# OLD-URC_ezFET_Lite.net
KiCad netlist of a schematic drawn in Altium Designer
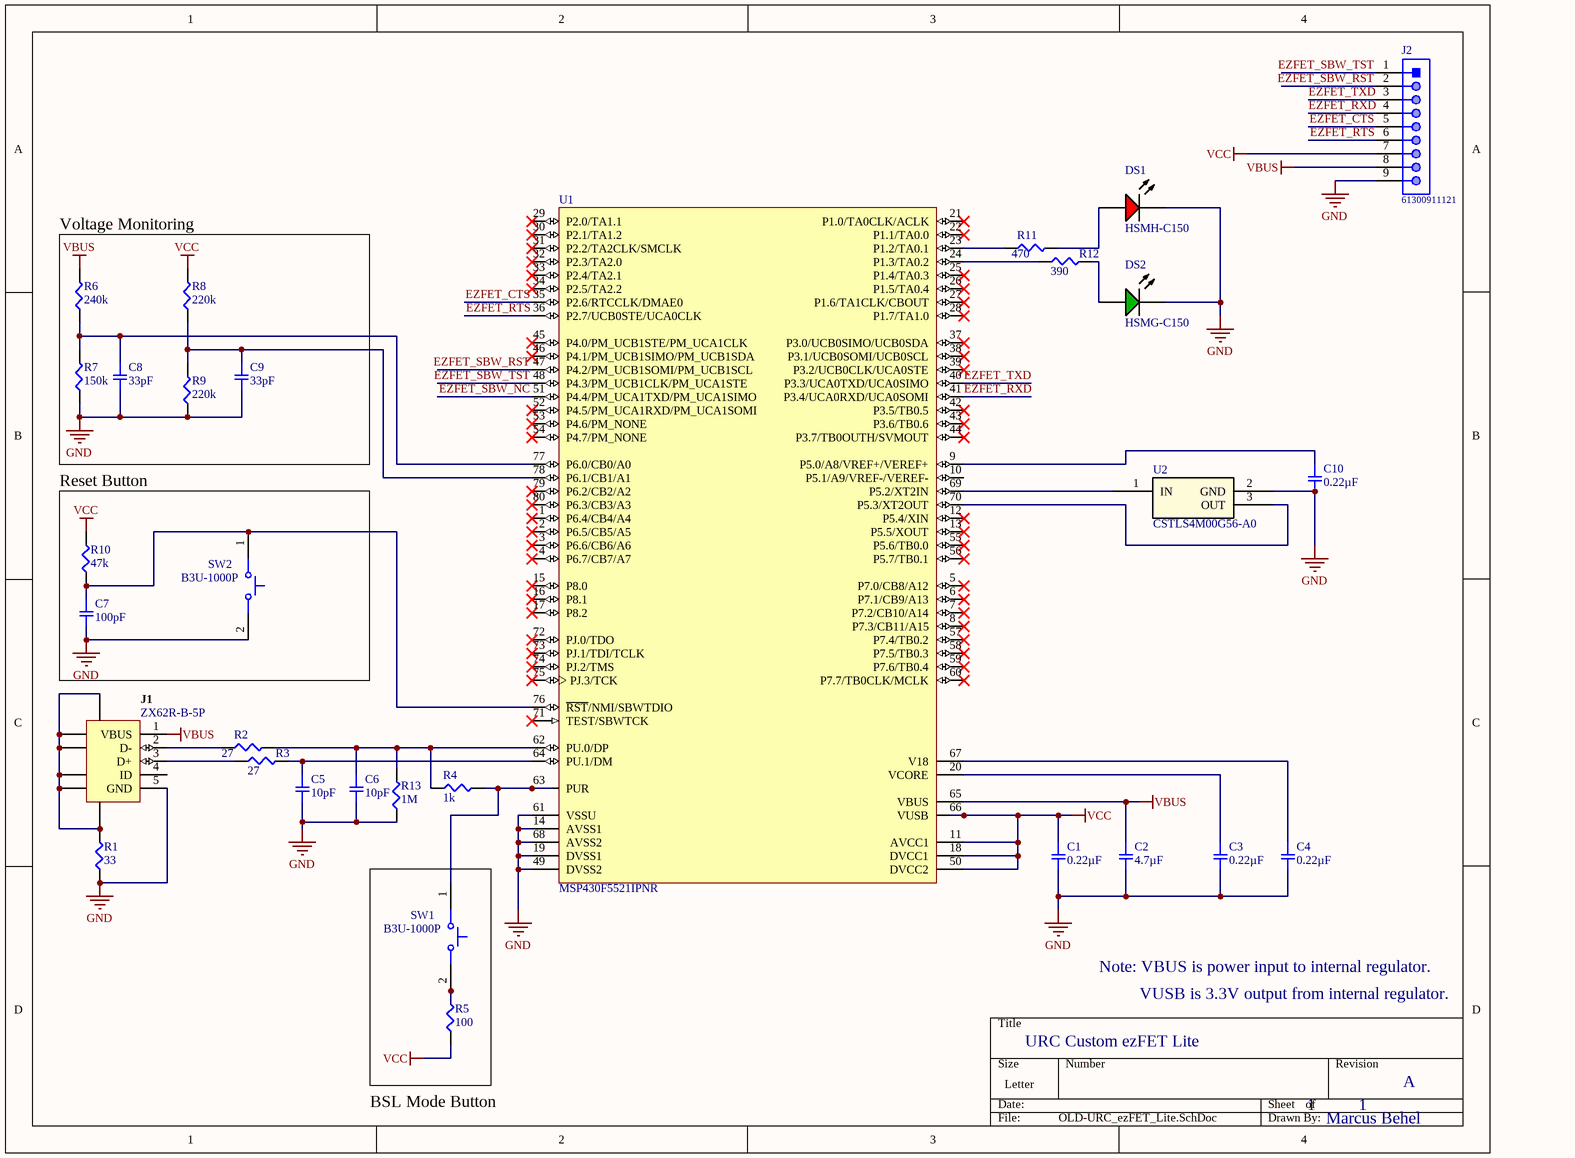
[diagram p0: OLD-URC_ezFET_Lite.SchDoc]

(export (version "E")
  (design (tool "Eeschema 10.0.6"))
  (components
    (comp (ref "C1")
      (value "0.22µF")
      (footprint "SMD-1206C")
      (description "CAP CER 0.22UF 50V X7R 1206")
      (fields
        (field (name "DIGI-KEY PART NUMBER") "490-8059-1-ND")
        (field (name "PART NUMBER") "GCM31MR71H224KA37L")
      )
      (libsource (lib "capacitor_murata_1206$") (part "GCM31MR71H224KA37L"))
    )
    (comp (ref "C2")
      (value "4.7µF")
      (footprint "SMD-1206C")
      (description "CAP CER 4.7UF 25V X7R 1206")
      (fields
        (field (name "DIGI-KEY PART NUMBER") "490-5808-1-ND")
        (field (name "PART NUMBER") "GCJ31CR71E475KA12L")
      )
      (libsource (lib "capacitor_murata_1206$") (part "GCJ31CR71E475KA12L"))
    )
    (comp (ref "C3")
      (value "0.22µF")
      (footprint "SMD-1206C")
      (description "CAP CER 0.22UF 50V X7R 1206")
      (fields
        (field (name "DIGI-KEY PART NUMBER") "490-8059-1-ND")
        (field (name "PART NUMBER") "GCM31MR71H224KA37L")
      )
      (libsource (lib "capacitor_murata_1206$") (part "GCM31MR71H224KA37L"))
    )
    (comp (ref "C4")
      (value "0.22µF")
      (footprint "SMD-1206C")
      (description "CAP CER 0.22UF 50V X7R 1206")
      (fields
        (field (name "DIGI-KEY PART NUMBER") "490-8059-1-ND")
        (field (name "PART NUMBER") "GCM31MR71H224KA37L")
      )
      (libsource (lib "capacitor_murata_1206$") (part "GCM31MR71H224KA37L"))
    )
    (comp (ref "C5")
      (value "10pF")
      (footprint "SMD-1206C")
      (description "CAP CER 10PF 630V U2J 1206")
      (fields
        (field (name "DIGI-KEY PART NUMBER") "490-5037-1-ND")
        (field (name "PART NUMBER") "GCM31A7U2J100JX01D")
      )
      (libsource (lib "capacitor_murata_1206$") (part "GCM31A7U2J100JX01D"))
    )
    (comp (ref "C6")
      (value "10pF")
      (footprint "SMD-1206C")
      (description "CAP CER 10PF 630V U2J 1206")
      (fields
        (field (name "DIGI-KEY PART NUMBER") "490-5037-1-ND")
        (field (name "PART NUMBER") "GCM31A7U2J100JX01D")
      )
      (libsource (lib "capacitor_murata_1206$") (part "GCM31A7U2J100JX01D"))
    )
    (comp (ref "C7")
      (value "100pF")
      (footprint "SMD-1206C")
      (description "CAP CER 100PF 630V U2J 1206")
      (fields
        (field (name "DIGI-KEY PART NUMBER") "490-5043-1-ND")
        (field (name "PART NUMBER") "GCM31A7U2J101JX01D")
      )
      (libsource (lib "capacitor_murata_1206$") (part "GCM31A7U2J101JX01D"))
    )
    (comp (ref "C8")
      (value "33pF")
      (footprint "SMD-1206C")
      (description "CAP CER 33PF 630V U2J 1206")
      (fields
        (field (name "DIGI-KEY PART NUMBER") "490-5040-1-ND")
        (field (name "PART NUMBER") "GCM31A7U2J330JX01D")
      )
      (libsource (lib "capacitor_murata_1206$") (part "GCM31A7U2J330JX01D"))
    )
    (comp (ref "C9")
      (value "33pF")
      (footprint "SMD-1206C")
      (description "CAP CER 33PF 630V U2J 1206")
      (fields
        (field (name "DIGI-KEY PART NUMBER") "490-5040-1-ND")
        (field (name "PART NUMBER") "GCM31A7U2J330JX01D")
      )
      (libsource (lib "capacitor_murata_1206$") (part "GCM31A7U2J330JX01D"))
    )
    (comp (ref "C10")
      (value "0.22µF")
      (footprint "SMD-1206C")
      (description "CAP CER 0.22UF 50V X7R 1206")
      (fields
        (field (name "DIGI-KEY PART NUMBER") "490-8059-1-ND")
        (field (name "PART NUMBER") "GCM31MR71H224KA37L")
      )
      (libsource (lib "capacitor_murata_1206$") (part "GCM31MR71H224KA37L"))
    )
    (comp (ref "DS1")
      (value "HSMH-C150")
      (footprint "AVAG-HSMX-C150_V")
      (description "LED Uni-Color Red, 65 mW, 25 mA, -40 to 85 degC, 2-Pin SMD, RoHS, Tape and Reel")
      (fields (field (name "MANUFACTURER") "Avago"))
      (libsource (lib "Altium Content Vault") (part "LED-RED-AK-2"))
    )
    (comp (ref "DS2")
      (value "HSMG-C150")
      (footprint "AVAG-HSMX-C150_V")
      (description "Chip LED, Green, 65 mW, 25 mA, -40 to 85 degC, 2-Pin SMD, RoHS, Tape and Reel")
      (fields (field (name "MANUFACTURER") "Avago"))
      (libsource (lib "Altium Content Vault") (part "LED_GREEN_A1K2-2"))
    )
    (comp (ref "J1")
      (value "ZX62R-B-5P")
      (footprint "HIRO-ZX62R-B-5P_V")
      (description "Connector; USBMicro-B,Reverse type, SMT; 5 Position; Right Angle")
      (libsource (lib "Altium Content Vault") (part "HIRO-ZX62R-B-5P-5"))
    )
    (comp (ref "J2")
      (value "61300911121")
      (footprint "61300911121")
      (description "THT Vertical Pin Header WR-PHD, Pitch 2.54 mm, Single Row, 9 pins")
      (fields (field (name "MANUFACTURER") "Wurth Elektronik") (field (name "PUBLISHER") "WurthElektronik"))
      (libsource (lib "Altium Content Vault") (part "WE-CN-1P-M-R9"))
    )
    (comp (ref "R1")
      (value "33")
      (footprint "SMD-1206-RES")
      (description "RES SMD 33 OHM 5% 2/3W 1206")
      (fields (field (name "PART NUMBER") "ERJ-P08J330V") (field (name "DIGI-KEY PART NUMBER") "P33ALCT-ND"))
      (libsource (lib "Panasonic_ERJ_1206") (part "ERJ-P08J330V"))
    )
    (comp (ref "R2")
      (value "27")
      (footprint "SMD-1206-RES")
      (description "RES SMD 27 OHM 5% 2/3W 1206")
      (fields (field (name "PART NUMBER") "ERJ-P08J270V") (field (name "DIGI-KEY PART NUMBER") "P27ALCT-ND"))
      (libsource (lib "Panasonic_ERJ_1206") (part "ERJ-P08J270V"))
    )
    (comp (ref "R3")
      (value "27")
      (footprint "SMD-1206-RES")
      (description "RES SMD 27 OHM 5% 2/3W 1206")
      (fields (field (name "PART NUMBER") "ERJ-P08J270V") (field (name "DIGI-KEY PART NUMBER") "P27ALCT-ND"))
      (libsource (lib "Panasonic_ERJ_1206") (part "ERJ-P08J270V"))
    )
    (comp (ref "R4")
      (value "1k")
      (footprint "SMD-1206-RES")
      (description "RES SMD 1K OHM 5% 2/3W 1206")
      (fields
        (field (name "PART NUMBER") "ERJ-P08J102V")
        (field (name "DIGI-KEY PART NUMBER") "P1.0KALCT-ND")
      )
      (libsource (lib "Panasonic_ERJ_1206") (part "ERJ-P08J102V"))
    )
    (comp (ref "R5")
      (value "100")
      (footprint "SMD-1206-RES")
      (description "RES SMD 100 OHM 1% 1/4W 1206")
      (fields (field (name "PART NUMBER") "ERJ-8ENF1000V") (field (name "DIGI-KEY PART NUMBER") "P100FCT-ND"))
      (libsource (lib "Panasonic_ERJ_1206") (part "ERJ-8ENF1000V"))
    )
    (comp (ref "R6")
      (value "240k")
      (footprint "SMD-1206-RES")
      (description "RES SMD 240K OHM 5% 2/3W 1206")
      (fields
        (field (name "PART NUMBER") "ERJ-P08J244V")
        (field (name "DIGI-KEY PART NUMBER") "P240KALCT-ND")
      )
      (libsource (lib "Panasonic_ERJ_1206") (part "ERJ-P08J244V"))
    )
    (comp (ref "R7")
      (value "150k")
      (footprint "SMD-1206-RES")
      (description "RES SMD 150K OHM 5% 2/3W 1206")
      (fields
        (field (name "PART NUMBER") "ERJ-P08J154V")
        (field (name "DIGI-KEY PART NUMBER") "P150KALCT-ND")
      )
      (libsource (lib "Panasonic_ERJ_1206") (part "ERJ-P08J154V"))
    )
    (comp (ref "R8")
      (value "220k")
      (footprint "SMD-1206-RES")
      (description "RES SMD 220K OHM 5% 2/3W 1206")
      (fields
        (field (name "PART NUMBER") "ERJ-P08J224V")
        (field (name "DIGI-KEY PART NUMBER") "P220KALCT-ND")
      )
      (libsource (lib "Panasonic_ERJ_1206") (part "ERJ-P08J224V"))
    )
    (comp (ref "R9")
      (value "220k")
      (footprint "SMD-1206-RES")
      (description "RES SMD 220K OHM 5% 2/3W 1206")
      (fields
        (field (name "PART NUMBER") "ERJ-P08J224V")
        (field (name "DIGI-KEY PART NUMBER") "P220KALCT-ND")
      )
      (libsource (lib "Panasonic_ERJ_1206") (part "ERJ-P08J224V"))
    )
    (comp (ref "R10")
      (value "47k")
      (footprint "SMD-1206-RES")
      (description "RES SMD 47K OHM 5% 1/4W 1206")
      (fields (field (name "PART NUMBER") "ERJ-8GEYJ473V") (field (name "DIGI-KEY PART NUMBER") "P47KECT-ND"))
      (libsource (lib "Panasonic_ERJ_1206") (part "ERJ-8GEYJ473V"))
    )
    (comp (ref "R11")
      (value "470")
      (footprint "SMD-1206-RES")
      (description "RES SMD 470 OHM 1% 1/4W 1206")
      (fields (field (name "PART NUMBER") "ERJ-8ENF4700V") (field (name "DIGI-KEY PART NUMBER") "P470FCT-ND"))
      (libsource (lib "Panasonic_ERJ_1206") (part "ERJ-8ENF4700V"))
    )
    (comp (ref "R12")
      (value "390")
      (footprint "SMD-1206-RES")
      (description "RES SMD 390 OHM 1% 1/4W 1206")
      (fields (field (name "PART NUMBER") "ERJ-8ENF3900V") (field (name "DIGI-KEY PART NUMBER") "P390FCT-ND"))
      (libsource (lib "Panasonic_ERJ_1206") (part "ERJ-8ENF3900V"))
    )
    (comp (ref "R13")
      (value "1M")
      (footprint "SMD-1206-RES")
      (description "RES SMD 1M OHM 5% 2/3W 1206")
      (fields
        (field (name "PART NUMBER") "ERJ-P08J105V")
        (field (name "DIGI-KEY PART NUMBER") "P1.0MALCT-ND")
      )
      (libsource (lib "Panasonic_ERJ_1206") (part "ERJ-P08J105V"))
    )
    (comp (ref "SW1")
      (value "B3U-1000P")
      (footprint "OMRON-B3U-1000_V")
      (description "Ultra-Small Tactile Switch, 0.05 A, 12 V, -25 to 70 degC, 2-Pin SMD, RoHS, Tape and Reel")
      (fields (field (name "MANUFACTURER") "Omron Electronic Components"))
      (libsource (lib "Altium Content Vault") (part "SW-SPST-NO-2"))
    )
    (comp (ref "SW2")
      (value "B3U-1000P")
      (footprint "OMRON-B3U-1000_V")
      (description "Ultra-Small Tactile Switch, 0.05 A, 12 V, -25 to 70 degC, 2-Pin SMD, RoHS, Tape and Reel")
      (fields (field (name "MANUFACTURER") "Omron Electronic Components"))
      (libsource (lib "Altium Content Vault") (part "SW-SPST-NO-2"))
    )
    (comp (ref "U1")
      (value "MSP430F5521IPNR")
      (footprint "PN0080A_M")
      (fields (field (name "MANUFACTURER") "Texas Instruments"))
      (libsource (lib "Altium Content Vault") (part "TI-MSP430F552X-PN80"))
    )
    (comp (ref "U2")
      (value "CSTLS4M00G56-A0")
      (footprint "CSTLS_G")
      (description "No Description Available")
      (fields (field (name "COPYRIGHT") "Copyright (C) 2018 Accelerated Designs. All rights reserved"))
      (libsource (lib "resonator") (part "CSTLS4M00G56-A0"))
    )
  )
  (nets
    (net (code "1") (name "/EZFET_CTS") (class "Default")
      (node (ref "J2") (pin "5") (pinfunction "5_5") (pintype "passive"))
      (node (ref "U1") (pin "35") (pinfunction "P2.6/RTCCLK/DMAE0_35") (pintype "bidirectional"))
    )
    (net (code "2") (name "/EZFET_RTS") (class "Default")
      (node (ref "J2") (pin "6") (pinfunction "6_6") (pintype "passive"))
      (node (ref "U1") (pin "36") (pinfunction "P2.7/UCB0STE/UCA0CLK_36") (pintype "bidirectional"))
    )
    (net (code "3") (name "/EZFET_RXD") (class "Default")
      (node (ref "J2") (pin "4") (pinfunction "4_4") (pintype "passive"))
      (node (ref "U1") (pin "41") (pinfunction "P3.4/UCA0RXD/UCA0SOMI_41") (pintype "bidirectional"))
    )
    (net (code "4") (name "/EZFET_SBW_NC") (class "Default")
      (node (ref "U1") (pin "51") (pinfunction "P4.4/PM_UCA1TXD/PM_UCA1SIMO_51") (pintype "bidirectional"))
    )
    (net (code "5") (name "/EZFET_SBW_RST") (class "Default")
      (node (ref "J2") (pin "2") (pinfunction "2_2") (pintype "passive"))
      (node (ref "U1") (pin "47") (pinfunction "P4.2/PM_UCB1SOMI/PM_UCB1SCL_47") (pintype "bidirectional"))
    )
    (net (code "6") (name "/EZFET_SBW_TST") (class "Default")
      (node (ref "J2") (pin "1") (pinfunction "1_1") (pintype "passive"))
      (node (ref "U1") (pin "48") (pinfunction "P4.3/PM_UCB1CLK/PM_UCA1STE_48") (pintype "bidirectional"))
    )
    (net (code "7") (name "/EZFET_TXD") (class "Default")
      (node (ref "J2") (pin "3") (pinfunction "3_3") (pintype "passive"))
      (node (ref "U1") (pin "40") (pinfunction "P3.3/UCA0TXD/UCA0SIMO_40") (pintype "bidirectional"))
    )
    (net (code "8") (name "GND") (class "Default")
      (node (ref "C1") (pin "2") (pinfunction "2_2") (pintype "passive"))
      (node (ref "C10") (pin "2") (pinfunction "2_2") (pintype "passive"))
      (node (ref "C2") (pin "2") (pinfunction "2_2") (pintype "passive"))
      (node (ref "C3") (pin "2") (pinfunction "2_2") (pintype "passive"))
      (node (ref "C4") (pin "2") (pinfunction "2_2") (pintype "passive"))
      (node (ref "C5") (pin "2") (pinfunction "2_2") (pintype "passive"))
      (node (ref "C6") (pin "2") (pinfunction "2_2") (pintype "passive"))
      (node (ref "C7") (pin "2") (pinfunction "2_2") (pintype "passive"))
      (node (ref "C8") (pin "2") (pinfunction "2_2") (pintype "passive"))
      (node (ref "C9") (pin "2") (pinfunction "2_2") (pintype "passive"))
      (node (ref "DS1") (pin "2") (pinfunction "K_2") (pintype "passive"))
      (node (ref "DS2") (pin "2") (pinfunction "K_2") (pintype "passive"))
      (node (ref "J1") (pin "5") (pinfunction "GND_5") (pintype "power_in"))
      (node (ref "J2") (pin "9") (pinfunction "9_9") (pintype "passive"))
      (node (ref "R1") (pin "1") (pinfunction "1_1") (pintype "passive"))
      (node (ref "R13") (pin "1") (pinfunction "1_1") (pintype "passive"))
      (node (ref "R7") (pin "1") (pinfunction "1_1") (pintype "passive"))
      (node (ref "R9") (pin "1") (pinfunction "1_1") (pintype "passive"))
      (node (ref "SW2") (pin "2") (pinfunction "2_2") (pintype "passive"))
      (node (ref "U1") (pin "14") (pinfunction "AVSS1_14") (pintype "power_in"))
      (node (ref "U1") (pin "19") (pinfunction "DVSS1_19") (pintype "power_in"))
      (node (ref "U1") (pin "49") (pinfunction "DVSS2_49") (pintype "power_in"))
      (node (ref "U1") (pin "61") (pinfunction "VSSU_61") (pintype "power_in"))
      (node (ref "U1") (pin "68") (pinfunction "AVSS2_68") (pintype "power_in"))
      (node (ref "U2") (pin "2") (pinfunction "GND_2") (pintype "passive"))
    )
    (net (code "9") (name "Net-(DS1-A)") (class "Default")
      (node (ref "DS1") (pin "1") (pinfunction "A_1") (pintype "passive"))
      (node (ref "R11") (pin "2") (pinfunction "2_2") (pintype "passive"))
    )
    (net (code "10") (name "Net-(DS2-A)") (class "Default")
      (node (ref "DS2") (pin "1") (pinfunction "A_1") (pintype "passive"))
      (node (ref "R12") (pin "2") (pinfunction "2_2") (pintype "passive"))
    )
    (net (code "11") (name "Net-(J1-D+)") (class "Default")
      (node (ref "J1") (pin "3") (pinfunction "D+_3") (pintype "bidirectional"))
      (node (ref "R3") (pin "1") (pinfunction "1_1") (pintype "passive"))
    )
    (net (code "12") (name "Net-(J1-D-)") (class "Default")
      (node (ref "J1") (pin "2") (pinfunction "D-_2") (pintype "bidirectional"))
      (node (ref "R2") (pin "1") (pinfunction "1_1") (pintype "passive"))
    )
    (net (code "13") (name "Net-(J1-SHLD-Pad10)") (class "Default")
      (node (ref "J1") (pin "10") (pinfunction "SHLD_10") (pintype "passive"))
      (node (ref "J1") (pin "11") (pinfunction "SHLD_11") (pintype "passive"))
      (node (ref "J1") (pin "6") (pinfunction "SHLD_6") (pintype "passive"))
      (node (ref "J1") (pin "7") (pinfunction "SHLD_7") (pintype "passive"))
      (node (ref "J1") (pin "8") (pinfunction "SHLD_8") (pintype "passive"))
      (node (ref "J1") (pin "9") (pinfunction "SHLD_9") (pintype "passive"))
      (node (ref "R1") (pin "2") (pinfunction "2_2") (pintype "passive"))
    )
    (net (code "14") (name "Net-(R5-Pad2)") (class "Default")
      (node (ref "R5") (pin "2") (pinfunction "2_2") (pintype "passive"))
      (node (ref "SW1") (pin "2") (pinfunction "2_2") (pintype "passive"))
    )
    (net (code "15") (name "Net-(U1-P1.2{slash}TA0.1)") (class "Default")
      (node (ref "R11") (pin "1") (pinfunction "1_1") (pintype "passive"))
      (node (ref "U1") (pin "23") (pinfunction "P1.2/TA0.1_23") (pintype "bidirectional"))
    )
    (net (code "16") (name "Net-(U1-P1.3{slash}TA0.2)") (class "Default")
      (node (ref "R12") (pin "1") (pinfunction "1_1") (pintype "passive"))
      (node (ref "U1") (pin "24") (pinfunction "P1.3/TA0.2_24") (pintype "bidirectional"))
    )
    (net (code "17") (name "Net-(U1-P5.0{slash}A8{slash}VREF+{slash}VEREF+)") (class "Default")
      (node (ref "C10") (pin "1") (pinfunction "1_1") (pintype "passive"))
      (node (ref "U1") (pin "9") (pinfunction "P5.0/A8/VREF+/VEREF+_9") (pintype "bidirectional"))
    )
    (net (code "18") (name "Net-(U1-P5.2{slash}XT2IN)") (class "Default")
      (node (ref "U1") (pin "69") (pinfunction "P5.2/XT2IN_69") (pintype "bidirectional"))
      (node (ref "U2") (pin "1") (pinfunction "IN_1") (pintype "passive"))
    )
    (net (code "19") (name "Net-(U1-P5.3{slash}XT2OUT)") (class "Default")
      (node (ref "U1") (pin "70") (pinfunction "P5.3/XT2OUT_70") (pintype "bidirectional"))
      (node (ref "U2") (pin "3") (pinfunction "OUT_3") (pintype "passive"))
    )
    (net (code "20") (name "Net-(U1-P6.0{slash}CB0{slash}A0)") (class "Default")
      (node (ref "C8") (pin "1") (pinfunction "1_1") (pintype "passive"))
      (node (ref "R6") (pin "1") (pinfunction "1_1") (pintype "passive"))
      (node (ref "R7") (pin "2") (pinfunction "2_2") (pintype "passive"))
      (node (ref "U1") (pin "77") (pinfunction "P6.0/CB0/A0_77") (pintype "bidirectional"))
    )
    (net (code "21") (name "Net-(U1-P6.1{slash}CB1{slash}A1)") (class "Default")
      (node (ref "C9") (pin "1") (pinfunction "1_1") (pintype "passive"))
      (node (ref "R8") (pin "1") (pinfunction "1_1") (pintype "passive"))
      (node (ref "R9") (pin "2") (pinfunction "2_2") (pintype "passive"))
      (node (ref "U1") (pin "78") (pinfunction "P6.1/CB1/A1_78") (pintype "bidirectional"))
    )
    (net (code "22") (name "Net-(U1-PU.0{slash}DP)") (class "Default")
      (node (ref "C6") (pin "1") (pinfunction "1_1") (pintype "passive"))
      (node (ref "R13") (pin "2") (pinfunction "2_2") (pintype "passive"))
      (node (ref "R2") (pin "2") (pinfunction "2_2") (pintype "passive"))
      (node (ref "R4") (pin "1") (pinfunction "1_1") (pintype "passive"))
      (node (ref "U1") (pin "62") (pinfunction "PU.0/DP_62") (pintype "bidirectional"))
    )
    (net (code "23") (name "Net-(U1-PU.1{slash}DM)") (class "Default")
      (node (ref "C5") (pin "1") (pinfunction "1_1") (pintype "passive"))
      (node (ref "R3") (pin "2") (pinfunction "2_2") (pintype "passive"))
      (node (ref "U1") (pin "64") (pinfunction "PU.1/DM_64") (pintype "bidirectional"))
    )
    (net (code "24") (name "Net-(U1-PUR)") (class "Default")
      (node (ref "R4") (pin "2") (pinfunction "2_2") (pintype "passive"))
      (node (ref "SW1") (pin "1") (pinfunction "1_1") (pintype "passive"))
      (node (ref "U1") (pin "63") (pinfunction "PUR_63") (pintype "passive"))
    )
    (net (code "25") (name "Net-(U1-V18)") (class "Default")
      (node (ref "C4") (pin "1") (pinfunction "1_1") (pintype "passive"))
      (node (ref "U1") (pin "67") (pinfunction "V18_67") (pintype "passive"))
    )
    (net (code "26") (name "Net-(U1-VCORE)") (class "Default")
      (node (ref "C3") (pin "1") (pinfunction "1_1") (pintype "passive"))
      (node (ref "U1") (pin "20") (pinfunction "VCORE_20") (pintype "passive"))
    )
    (net (code "27") (name "Net-(U1-~{RST}{slash}NMI{slash}SBWTDIO)") (class "Default")
      (node (ref "C7") (pin "1") (pinfunction "1_1") (pintype "passive"))
      (node (ref "R10") (pin "1") (pinfunction "1_1") (pintype "passive"))
      (node (ref "SW2") (pin "1") (pinfunction "1_1") (pintype "passive"))
      (node (ref "U1") (pin "76") (pinfunction "~{RST}/NMI/SBWTDIO_76") (pintype "bidirectional"))
    )
    (net (code "28") (name "VBUS") (class "Default")
      (node (ref "C2") (pin "1") (pinfunction "1_1") (pintype "passive"))
      (node (ref "J1") (pin "1") (pinfunction "VBUS_1") (pintype "power_in"))
      (node (ref "J2") (pin "8") (pinfunction "8_8") (pintype "passive"))
      (node (ref "R6") (pin "2") (pinfunction "2_2") (pintype "passive"))
      (node (ref "U1") (pin "65") (pinfunction "VBUS_65") (pintype "power_in"))
    )
    (net (code "29") (name "VCC") (class "Default")
      (node (ref "C1") (pin "1") (pinfunction "1_1") (pintype "passive"))
      (node (ref "J2") (pin "7") (pinfunction "7_7") (pintype "passive"))
      (node (ref "R10") (pin "2") (pinfunction "2_2") (pintype "passive"))
      (node (ref "R5") (pin "1") (pinfunction "1_1") (pintype "passive"))
      (node (ref "R8") (pin "2") (pinfunction "2_2") (pintype "passive"))
      (node (ref "U1") (pin "11") (pinfunction "AVCC1_11") (pintype "power_in"))
      (node (ref "U1") (pin "18") (pinfunction "DVCC1_18") (pintype "power_in"))
      (node (ref "U1") (pin "50") (pinfunction "DVCC2_50") (pintype "power_in"))
      (node (ref "U1") (pin "66") (pinfunction "VUSB_66") (pintype "power_in"))
    )
    (net (code "30") (name "unconnected-(J1-ID-Pad4)") (class "Default")
      (node (ref "J1") (pin "4") (pinfunction "ID_4") (pintype "passive"))
    )
    (net (code "31") (name "unconnected-(U1-P1.0{slash}TA0CLK{slash}ACLK-Pad21)") (class "Default")
      (node (ref "U1") (pin "21") (pinfunction "P1.0/TA0CLK/ACLK_21") (pintype "bidirectional+no_connect"))
    )
    (net (code "32") (name "unconnected-(U1-P1.1{slash}TA0.0-Pad22)") (class "Default")
      (node (ref "U1") (pin "22") (pinfunction "P1.1/TA0.0_22") (pintype "bidirectional+no_connect"))
    )
    (net (code "33") (name "unconnected-(U1-P1.4{slash}TA0.3-Pad25)") (class "Default")
      (node (ref "U1") (pin "25") (pinfunction "P1.4/TA0.3_25") (pintype "bidirectional+no_connect"))
    )
    (net (code "34") (name "unconnected-(U1-P1.5{slash}TA0.4-Pad26)") (class "Default")
      (node (ref "U1") (pin "26") (pinfunction "P1.5/TA0.4_26") (pintype "bidirectional+no_connect"))
    )
    (net (code "35") (name "unconnected-(U1-P1.6{slash}TA1CLK{slash}CBOUT-Pad27)") (class "Default")
      (node (ref "U1") (pin "27") (pinfunction "P1.6/TA1CLK/CBOUT_27") (pintype "bidirectional+no_connect"))
    )
    (net (code "36") (name "unconnected-(U1-P1.7{slash}TA1.0-Pad28)") (class "Default")
      (node (ref "U1") (pin "28") (pinfunction "P1.7/TA1.0_28") (pintype "bidirectional+no_connect"))
    )
    (net (code "37") (name "unconnected-(U1-P2.0{slash}TA1.1-Pad29)") (class "Default")
      (node (ref "U1") (pin "29") (pinfunction "P2.0/TA1.1_29") (pintype "bidirectional+no_connect"))
    )
    (net (code "38") (name "unconnected-(U1-P2.1{slash}TA1.2-Pad30)") (class "Default")
      (node (ref "U1") (pin "30") (pinfunction "P2.1/TA1.2_30") (pintype "bidirectional+no_connect"))
    )
    (net (code "39") (name "unconnected-(U1-P2.2{slash}TA2CLK{slash}SMCLK-Pad31)") (class "Default")
      (node (ref "U1") (pin "31") (pinfunction "P2.2/TA2CLK/SMCLK_31") (pintype "bidirectional+no_connect"))
    )
    (net (code "40") (name "unconnected-(U1-P2.3{slash}TA2.0-Pad32)") (class "Default")
      (node (ref "U1") (pin "32") (pinfunction "P2.3/TA2.0_32") (pintype "bidirectional+no_connect"))
    )
    (net (code "41") (name "unconnected-(U1-P2.4{slash}TA2.1-Pad33)") (class "Default")
      (node (ref "U1") (pin "33") (pinfunction "P2.4/TA2.1_33") (pintype "bidirectional+no_connect"))
    )
    (net (code "42") (name "unconnected-(U1-P2.5{slash}TA2.2-Pad34)") (class "Default")
      (node (ref "U1") (pin "34") (pinfunction "P2.5/TA2.2_34") (pintype "bidirectional+no_connect"))
    )
    (net (code "43") (name "unconnected-(U1-P3.0{slash}UCB0SIMO{slash}UCB0SDA-Pad37)") (class "Default")
      (node (ref "U1") (pin "37") (pinfunction "P3.0/UCB0SIMO/UCB0SDA_37") (pintype "bidirectional+no_connect"))
    )
    (net (code "44") (name "unconnected-(U1-P3.1{slash}UCB0SOMI{slash}UCB0SCL-Pad38)") (class "Default")
      (node (ref "U1") (pin "38") (pinfunction "P3.1/UCB0SOMI/UCB0SCL_38") (pintype "bidirectional+no_connect"))
    )
    (net (code "45") (name "unconnected-(U1-P3.2{slash}UCB0CLK{slash}UCA0STE-Pad39)") (class "Default")
      (node (ref "U1") (pin "39") (pinfunction "P3.2/UCB0CLK/UCA0STE_39") (pintype "bidirectional+no_connect"))
    )
    (net (code "46") (name "unconnected-(U1-P3.5{slash}TB0.5-Pad42)") (class "Default")
      (node (ref "U1") (pin "42") (pinfunction "P3.5/TB0.5_42") (pintype "bidirectional+no_connect"))
    )
    (net (code "47") (name "unconnected-(U1-P3.6{slash}TB0.6-Pad43)") (class "Default")
      (node (ref "U1") (pin "43") (pinfunction "P3.6/TB0.6_43") (pintype "bidirectional+no_connect"))
    )
    (net (code "48") (name "unconnected-(U1-P3.7{slash}TB0OUTH{slash}SVMOUT-Pad44)") (class "Default")
      (node (ref "U1") (pin "44") (pinfunction "P3.7/TB0OUTH/SVMOUT_44") (pintype "bidirectional+no_connect"))
    )
    (net (code "49") (name "unconnected-(U1-P4.0{slash}PM_UCB1STE{slash}PM_UCA1CLK-Pad45)") (class "Default")
      (node (ref "U1") (pin "45") (pinfunction "P4.0/PM_UCB1STE/PM_UCA1CLK_45") (pintype "bidirectional+no_connect"))
    )
    (net (code "50") (name "unconnected-(U1-P4.1{slash}PM_UCB1SIMO{slash}PM_UCB1SDA-Pad46)") (class "Default")
      (node (ref "U1") (pin "46") (pinfunction "P4.1/PM_UCB1SIMO/PM_UCB1SDA_46") (pintype "bidirectional+no_connect"))
    )
    (net (code "51") (name "unconnected-(U1-P4.5{slash}PM_UCA1RXD{slash}PM_UCA1SOMI-Pad52)") (class "Default")
      (node (ref "U1") (pin "52") (pinfunction "P4.5/PM_UCA1RXD/PM_UCA1SOMI_52") (pintype "bidirectional+no_connect"))
    )
    (net (code "52") (name "unconnected-(U1-P4.6{slash}PM_NONE-Pad53)") (class "Default")
      (node (ref "U1") (pin "53") (pinfunction "P4.6/PM_NONE_53") (pintype "bidirectional+no_connect"))
    )
    (net (code "53") (name "unconnected-(U1-P4.7{slash}PM_NONE-Pad54)") (class "Default")
      (node (ref "U1") (pin "54") (pinfunction "P4.7/PM_NONE_54") (pintype "bidirectional+no_connect"))
    )
    (net (code "54") (name "unconnected-(U1-P5.1{slash}A9{slash}VREF-{slash}VEREF--Pad10)") (class "Default")
      (node (ref "U1") (pin "10") (pinfunction "P5.1/A9/VREF-/VEREF-_10") (pintype "bidirectional"))
    )
    (net (code "55") (name "unconnected-(U1-P5.4{slash}XIN-Pad12)") (class "Default")
      (node (ref "U1") (pin "12") (pinfunction "P5.4/XIN_12") (pintype "bidirectional+no_connect"))
    )
    (net (code "56") (name "unconnected-(U1-P5.5{slash}XOUT-Pad13)") (class "Default")
      (node (ref "U1") (pin "13") (pinfunction "P5.5/XOUT_13") (pintype "bidirectional+no_connect"))
    )
    (net (code "57") (name "unconnected-(U1-P5.6{slash}TB0.0-Pad55)") (class "Default")
      (node (ref "U1") (pin "55") (pinfunction "P5.6/TB0.0_55") (pintype "bidirectional+no_connect"))
    )
    (net (code "58") (name "unconnected-(U1-P5.7{slash}TB0.1-Pad56)") (class "Default")
      (node (ref "U1") (pin "56") (pinfunction "P5.7/TB0.1_56") (pintype "bidirectional+no_connect"))
    )
    (net (code "59") (name "unconnected-(U1-P6.2{slash}CB2{slash}A2-Pad79)") (class "Default")
      (node (ref "U1") (pin "79") (pinfunction "P6.2/CB2/A2_79") (pintype "bidirectional+no_connect"))
    )
    (net (code "60") (name "unconnected-(U1-P6.3{slash}CB3{slash}A3-Pad80)") (class "Default")
      (node (ref "U1") (pin "80") (pinfunction "P6.3/CB3/A3_80") (pintype "bidirectional+no_connect"))
    )
    (net (code "61") (name "unconnected-(U1-P6.4{slash}CB4{slash}A4-Pad1)") (class "Default")
      (node (ref "U1") (pin "1") (pinfunction "P6.4/CB4/A4_1") (pintype "bidirectional+no_connect"))
    )
    (net (code "62") (name "unconnected-(U1-P6.5{slash}CB5{slash}A5-Pad2)") (class "Default")
      (node (ref "U1") (pin "2") (pinfunction "P6.5/CB5/A5_2") (pintype "bidirectional+no_connect"))
    )
    (net (code "63") (name "unconnected-(U1-P6.6{slash}CB6{slash}A6-Pad3)") (class "Default")
      (node (ref "U1") (pin "3") (pinfunction "P6.6/CB6/A6_3") (pintype "bidirectional+no_connect"))
    )
    (net (code "64") (name "unconnected-(U1-P6.7{slash}CB7{slash}A7-Pad4)") (class "Default")
      (node (ref "U1") (pin "4") (pinfunction "P6.7/CB7/A7_4") (pintype "bidirectional+no_connect"))
    )
    (net (code "65") (name "unconnected-(U1-P7.0{slash}CB8{slash}A12-Pad5)") (class "Default")
      (node (ref "U1") (pin "5") (pinfunction "P7.0/CB8/A12_5") (pintype "bidirectional+no_connect"))
    )
    (net (code "66") (name "unconnected-(U1-P7.1{slash}CB9{slash}A13-Pad6)") (class "Default")
      (node (ref "U1") (pin "6") (pinfunction "P7.1/CB9/A13_6") (pintype "bidirectional+no_connect"))
    )
    (net (code "67") (name "unconnected-(U1-P7.2{slash}CB10{slash}A14-Pad7)") (class "Default")
      (node (ref "U1") (pin "7") (pinfunction "P7.2/CB10/A14_7") (pintype "bidirectional+no_connect"))
    )
    (net (code "68") (name "unconnected-(U1-P7.3{slash}CB11{slash}A15-Pad8)") (class "Default")
      (node (ref "U1") (pin "8") (pinfunction "P7.3/CB11/A15_8") (pintype "bidirectional+no_connect"))
    )
    (net (code "69") (name "unconnected-(U1-P7.4{slash}TB0.2-Pad57)") (class "Default")
      (node (ref "U1") (pin "57") (pinfunction "P7.4/TB0.2_57") (pintype "bidirectional+no_connect"))
    )
    (net (code "70") (name "unconnected-(U1-P7.5{slash}TB0.3-Pad58)") (class "Default")
      (node (ref "U1") (pin "58") (pinfunction "P7.5/TB0.3_58") (pintype "bidirectional+no_connect"))
    )
    (net (code "71") (name "unconnected-(U1-P7.6{slash}TB0.4-Pad59)") (class "Default")
      (node (ref "U1") (pin "59") (pinfunction "P7.6/TB0.4_59") (pintype "bidirectional+no_connect"))
    )
    (net (code "72") (name "unconnected-(U1-P7.7{slash}TB0CLK{slash}MCLK-Pad60)") (class "Default")
      (node (ref "U1") (pin "60") (pinfunction "P7.7/TB0CLK/MCLK_60") (pintype "bidirectional+no_connect"))
    )
    (net (code "73") (name "unconnected-(U1-P8.0-Pad15)") (class "Default")
      (node (ref "U1") (pin "15") (pinfunction "P8.0_15") (pintype "bidirectional+no_connect"))
    )
    (net (code "74") (name "unconnected-(U1-P8.1-Pad16)") (class "Default")
      (node (ref "U1") (pin "16") (pinfunction "P8.1_16") (pintype "bidirectional+no_connect"))
    )
    (net (code "75") (name "unconnected-(U1-P8.2-Pad17)") (class "Default")
      (node (ref "U1") (pin "17") (pinfunction "P8.2_17") (pintype "bidirectional+no_connect"))
    )
    (net (code "76") (name "unconnected-(U1-PJ.0{slash}TDO-Pad72)") (class "Default")
      (node (ref "U1") (pin "72") (pinfunction "PJ.0/TDO_72") (pintype "bidirectional+no_connect"))
    )
    (net (code "77") (name "unconnected-(U1-PJ.1{slash}TDI{slash}TCLK-Pad73)") (class "Default")
      (node (ref "U1") (pin "73") (pinfunction "PJ.1/TDI/TCLK_73") (pintype "bidirectional+no_connect"))
    )
    (net (code "78") (name "unconnected-(U1-PJ.2{slash}TMS-Pad74)") (class "Default")
      (node (ref "U1") (pin "74") (pinfunction "PJ.2/TMS_74") (pintype "bidirectional+no_connect"))
    )
    (net (code "79") (name "unconnected-(U1-PJ.3{slash}TCK-Pad75)") (class "Default")
      (node (ref "U1") (pin "75") (pinfunction "PJ.3/TCK_75") (pintype "bidirectional+no_connect"))
    )
    (net (code "80") (name "unconnected-(U1-TEST{slash}SBWTCK-Pad71)") (class "Default")
      (node (ref "U1") (pin "71") (pinfunction "TEST/SBWTCK_71") (pintype "input+no_connect"))
    )
  )
)
